# BLDC_Schem.net
KiCad netlist of a schematic drawn in Altium Designer
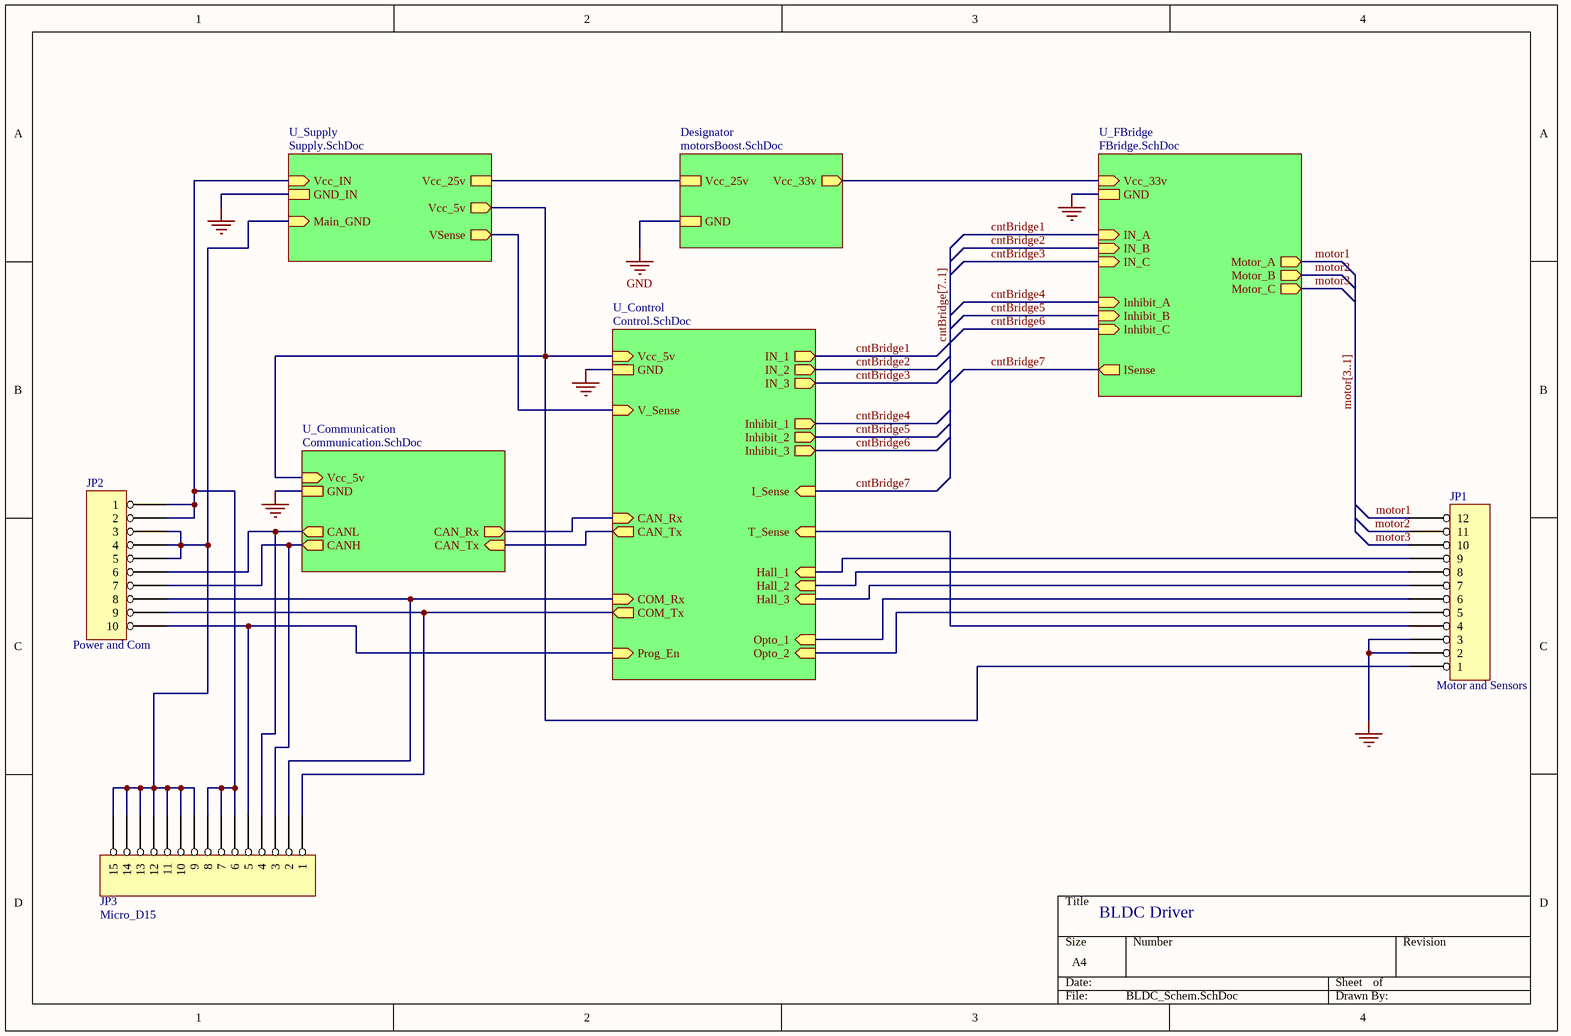
[diagram p0: BLDC_Schem.SchDoc]

(export (version "E")
  (design (tool "Eeschema 10.0.6"))
  (components
    (comp (ref "JP1")
      (value "Motor and Sensors")
      (footprint "HDR1X12")
      (libsource (lib "Sch_Lib_24") (part "HEADER 12"))
    )
    (comp (ref "JP2")
      (value "Power and Com")
      (footprint "HDR1X10")
      (libsource (lib "Sch_Lib_24") (part "HEADER 10"))
    )
    (comp (ref "JP3")
      (value "Micro_D15")
      (footprint "Micro_D")
      (libsource (lib "Sch_Lib_27") (part "HEADER 15"))
    )
  )
  (nets
    (net (code "1") (name "/CANH") (class "Default")
      (node (ref "JP2") (pin "7") (pinfunction "7_7") (pintype "passive"))
      (node (ref "JP3") (pin "3") (pinfunction "3_3") (pintype "passive"))
    )
    (net (code "2") (name "/CANL") (class "Default")
      (node (ref "JP2") (pin "6") (pinfunction "6_6") (pintype "passive"))
      (node (ref "JP3") (pin "4") (pinfunction "4_4") (pintype "passive"))
    )
    (net (code "5") (name "/COM_Rx") (class "Default")
      (node (ref "JP2") (pin "8") (pinfunction "8_8") (pintype "passive"))
      (node (ref "JP3") (pin "2") (pinfunction "2_2") (pintype "passive"))
    )
    (net (code "6") (name "/COM_Tx") (class "Default")
      (node (ref "JP2") (pin "9") (pinfunction "9_9") (pintype "passive"))
      (node (ref "JP3") (pin "1") (pinfunction "1_1") (pintype "passive"))
    )
    (net (code "7") (name "/Hall_1") (class "Default")
      (node (ref "JP1") (pin "9") (pinfunction "9_9") (pintype "passive"))
    )
    (net (code "8") (name "/Hall_2") (class "Default")
      (node (ref "JP1") (pin "8") (pinfunction "8_8") (pintype "passive"))
    )
    (net (code "9") (name "/Hall_3") (class "Default")
      (node (ref "JP1") (pin "7") (pinfunction "7_7") (pintype "passive"))
    )
    (net (code "10") (name "/Main_GND") (class "Default")
      (node (ref "JP2") (pin "3") (pinfunction "3_3") (pintype "passive"))
      (node (ref "JP2") (pin "4") (pinfunction "4_4") (pintype "passive"))
      (node (ref "JP2") (pin "5") (pinfunction "5_5") (pintype "passive"))
      (node (ref "JP3") (pin "10") (pinfunction "10_10") (pintype "passive"))
      (node (ref "JP3") (pin "11") (pinfunction "11_11") (pintype "passive"))
      (node (ref "JP3") (pin "12") (pinfunction "12_12") (pintype "passive"))
      (node (ref "JP3") (pin "13") (pinfunction "13_13") (pintype "passive"))
      (node (ref "JP3") (pin "14") (pinfunction "14_14") (pintype "passive"))
      (node (ref "JP3") (pin "15") (pinfunction "15_15") (pintype "passive"))
      (node (ref "JP3") (pin "9") (pinfunction "9_9") (pintype "passive"))
    )
    (net (code "11") (name "/Opto_1") (class "Default")
      (node (ref "JP1") (pin "6") (pinfunction "6_6") (pintype "passive"))
    )
    (net (code "12") (name "/Opto_2") (class "Default")
      (node (ref "JP1") (pin "5") (pinfunction "5_5") (pintype "passive"))
    )
    (net (code "13") (name "/Prog_En") (class "Default")
      (node (ref "JP2") (pin "10") (pinfunction "10_10") (pintype "passive"))
      (node (ref "JP3") (pin "5") (pinfunction "5_5") (pintype "passive"))
    )
    (net (code "14") (name "/T_Sense") (class "Default")
      (node (ref "JP1") (pin "4") (pinfunction "4_4") (pintype "passive"))
    )
    (net (code "16") (name "/Vcc_5v") (class "Default")
      (node (ref "JP1") (pin "1") (pinfunction "1_1") (pintype "passive"))
    )
    (net (code "19") (name "/Vcc_IN") (class "Default")
      (node (ref "JP2") (pin "1") (pinfunction "1_1") (pintype "passive"))
      (node (ref "JP2") (pin "2") (pinfunction "2_2") (pintype "passive"))
      (node (ref "JP3") (pin "6") (pinfunction "6_6") (pintype "passive"))
      (node (ref "JP3") (pin "7") (pinfunction "7_7") (pintype "passive"))
      (node (ref "JP3") (pin "8") (pinfunction "8_8") (pintype "passive"))
    )
    (net (code "28") (name "/motor1") (class "Default")
      (node (ref "JP1") (pin "12") (pinfunction "12_12") (pintype "passive"))
    )
    (net (code "29") (name "/motor2") (class "Default")
      (node (ref "JP1") (pin "11") (pinfunction "11_11") (pintype "passive"))
    )
    (net (code "30") (name "/motor3") (class "Default")
      (node (ref "JP1") (pin "10") (pinfunction "10_10") (pintype "passive"))
    )
    (net (code "32") (name "GND") (class "Default")
      (node (ref "JP1") (pin "2") (pinfunction "2_2") (pintype "passive"))
      (node (ref "JP1") (pin "3") (pinfunction "3_3") (pintype "passive"))
    )
  )
)
